# haystack_mic.net
KiCad netlist of a schematic drawn in EAGLE
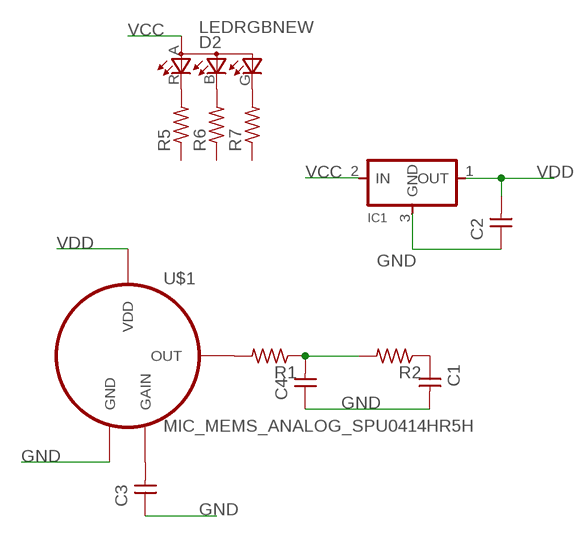
[diagram p0: schematic, sheet 1]

(export (version "E")
  (design (tool "Eeschema 10.0.6"))
  (components
    (comp (ref "C1")
      (value "CAP-UNPOLARIZED")
      (footprint "eagle-import:C1206")
      (libsource (lib "eagle-import") (part "CAP-UNPOLARIZED"))
    )
    (comp (ref "C2")
      (value "CAP-UNPOLARIZED")
      (footprint "eagle-import:C1206")
      (libsource (lib "eagle-import") (part "CAP-UNPOLARIZED"))
    )
    (comp (ref "C3")
      (value "CAP-UNPOLARIZED")
      (footprint "eagle-import:C1206")
      (libsource (lib "eagle-import") (part "CAP-UNPOLARIZED"))
    )
    (comp (ref "C4")
      (value "CAP-UNPOLARIZED")
      (footprint "eagle-import:C1206")
      (libsource (lib "eagle-import") (part "CAP-UNPOLARIZED"))
    )
    (comp (ref "D2")
      (value "LEDRGBNEW")
      (footprint "eagle-import:P-LCC-4")
      (libsource (lib "eagle-import") (part "LEDRGBNEW"))
    )
    (comp (ref "IC1")
      (value "REGULATORSOT23")
      (footprint "eagle-import:SOT23")
      (libsource (lib "eagle-import") (part "REGULATORSOT23"))
    )
    (comp (ref "R1")
      (value "RES-US1206")
      (footprint "eagle-import:R1206")
      (libsource (lib "eagle-import") (part "RES-US1206"))
    )
    (comp (ref "R2")
      (value "RES-US1206")
      (footprint "eagle-import:R1206")
      (libsource (lib "eagle-import") (part "RES-US1206"))
    )
    (comp (ref "R5")
      (value "RES-US1206")
      (footprint "eagle-import:R1206")
      (libsource (lib "eagle-import") (part "RES-US1206"))
    )
    (comp (ref "R6")
      (value "RES-US1206")
      (footprint "eagle-import:R1206")
      (libsource (lib "eagle-import") (part "RES-US1206"))
    )
    (comp (ref "R7")
      (value "RES-US1206")
      (footprint "eagle-import:R1206")
      (libsource (lib "eagle-import") (part "RES-US1206"))
    )
    (comp (ref "U$1")
      (value "MIC_MEMS_ANALOG_SPU0414HR5H")
      (footprint "eagle-import:MIC_MEMS_ANALOG_SPU0414HR5H")
      (libsource (lib "eagle-import") (part "MIC_MEMS_ANALOG_SPU0414HR5H"))
    )
  )
  (nets
    (net (code "1") (name "/GND") (class "Default")
      (node (ref "C1") (pin "2") (pinfunction "2_2") (pintype "passive"))
      (node (ref "C2") (pin "1") (pinfunction "1_1") (pintype "passive"))
      (node (ref "C3") (pin "1") (pinfunction "1_1") (pintype "passive"))
      (node (ref "C4") (pin "1") (pinfunction "1_1") (pintype "passive"))
      (node (ref "IC1") (pin "3") (pinfunction "GND_3") (pintype "bidirectional"))
      (node (ref "U$1") (pin "2") (pinfunction "GND_2") (pintype "power_in"))
    )
    (net (code "2") (name "/VCC") (class "Default")
      (node (ref "D2") (pin "A") (pinfunction "A2_A") (pintype "passive"))
      (node (ref "IC1") (pin "2") (pinfunction "IN_2") (pintype "bidirectional"))
    )
    (net (code "3") (name "/VDD") (class "Default")
      (node (ref "C2") (pin "2") (pinfunction "2_2") (pintype "passive"))
      (node (ref "IC1") (pin "1") (pinfunction "OUT_1") (pintype "bidirectional"))
      (node (ref "U$1") (pin "1") (pinfunction "VDD_1") (pintype "power_in"))
    )
    (net (code "4") (name "Net-(C1-Pad1)") (class "Default")
      (node (ref "C1") (pin "1") (pinfunction "1_1") (pintype "passive"))
      (node (ref "R2") (pin "1") (pinfunction "1_1") (pintype "passive"))
    )
    (net (code "5") (name "Net-(C4-Pad2)") (class "Default")
      (node (ref "C4") (pin "2") (pinfunction "2_2") (pintype "passive"))
      (node (ref "R1") (pin "1") (pinfunction "1_1") (pintype "passive"))
      (node (ref "R2") (pin "2") (pinfunction "2_2") (pintype "passive"))
    )
    (net (code "6") (name "Net-(D2-CBLUE)") (class "Default")
      (node (ref "D2") (pin "B") (pinfunction "CBLUE_B") (pintype "passive"))
      (node (ref "R6") (pin "2") (pinfunction "2_2") (pintype "passive"))
    )
    (net (code "7") (name "Net-(D2-CGREEN)") (class "Default")
      (node (ref "D2") (pin "G") (pinfunction "CGREEN_G") (pintype "passive"))
      (node (ref "R7") (pin "2") (pinfunction "2_2") (pintype "passive"))
    )
    (net (code "8") (name "Net-(D2-CRED)") (class "Default")
      (node (ref "D2") (pin "R") (pinfunction "CRED_R") (pintype "passive"))
      (node (ref "R5") (pin "2") (pinfunction "2_2") (pintype "passive"))
    )
    (net (code "9") (name "Net-(U$1-GAIN)") (class "Default")
      (node (ref "C3") (pin "2") (pinfunction "2_2") (pintype "passive"))
      (node (ref "U$1") (pin "3") (pinfunction "GAIN_3") (pintype "bidirectional"))
    )
    (net (code "10") (name "Net-(U$1-OUT)") (class "Default")
      (node (ref "R1") (pin "2") (pinfunction "2_2") (pintype "passive"))
      (node (ref "U$1") (pin "4") (pinfunction "OUT_4") (pintype "output"))
    )
    (net (code "11") (name "unconnected-(R5-Pad1)") (class "Default")
      (node (ref "R5") (pin "1") (pinfunction "1_1") (pintype "passive"))
    )
    (net (code "12") (name "unconnected-(R6-Pad1)") (class "Default")
      (node (ref "R6") (pin "1") (pinfunction "1_1") (pintype "passive"))
    )
    (net (code "13") (name "unconnected-(R7-Pad1)") (class "Default")
      (node (ref "R7") (pin "1") (pinfunction "1_1") (pintype "passive"))
    )
  )
)
